# auduino.net
KiCad netlist of a schematic drawn in EAGLE
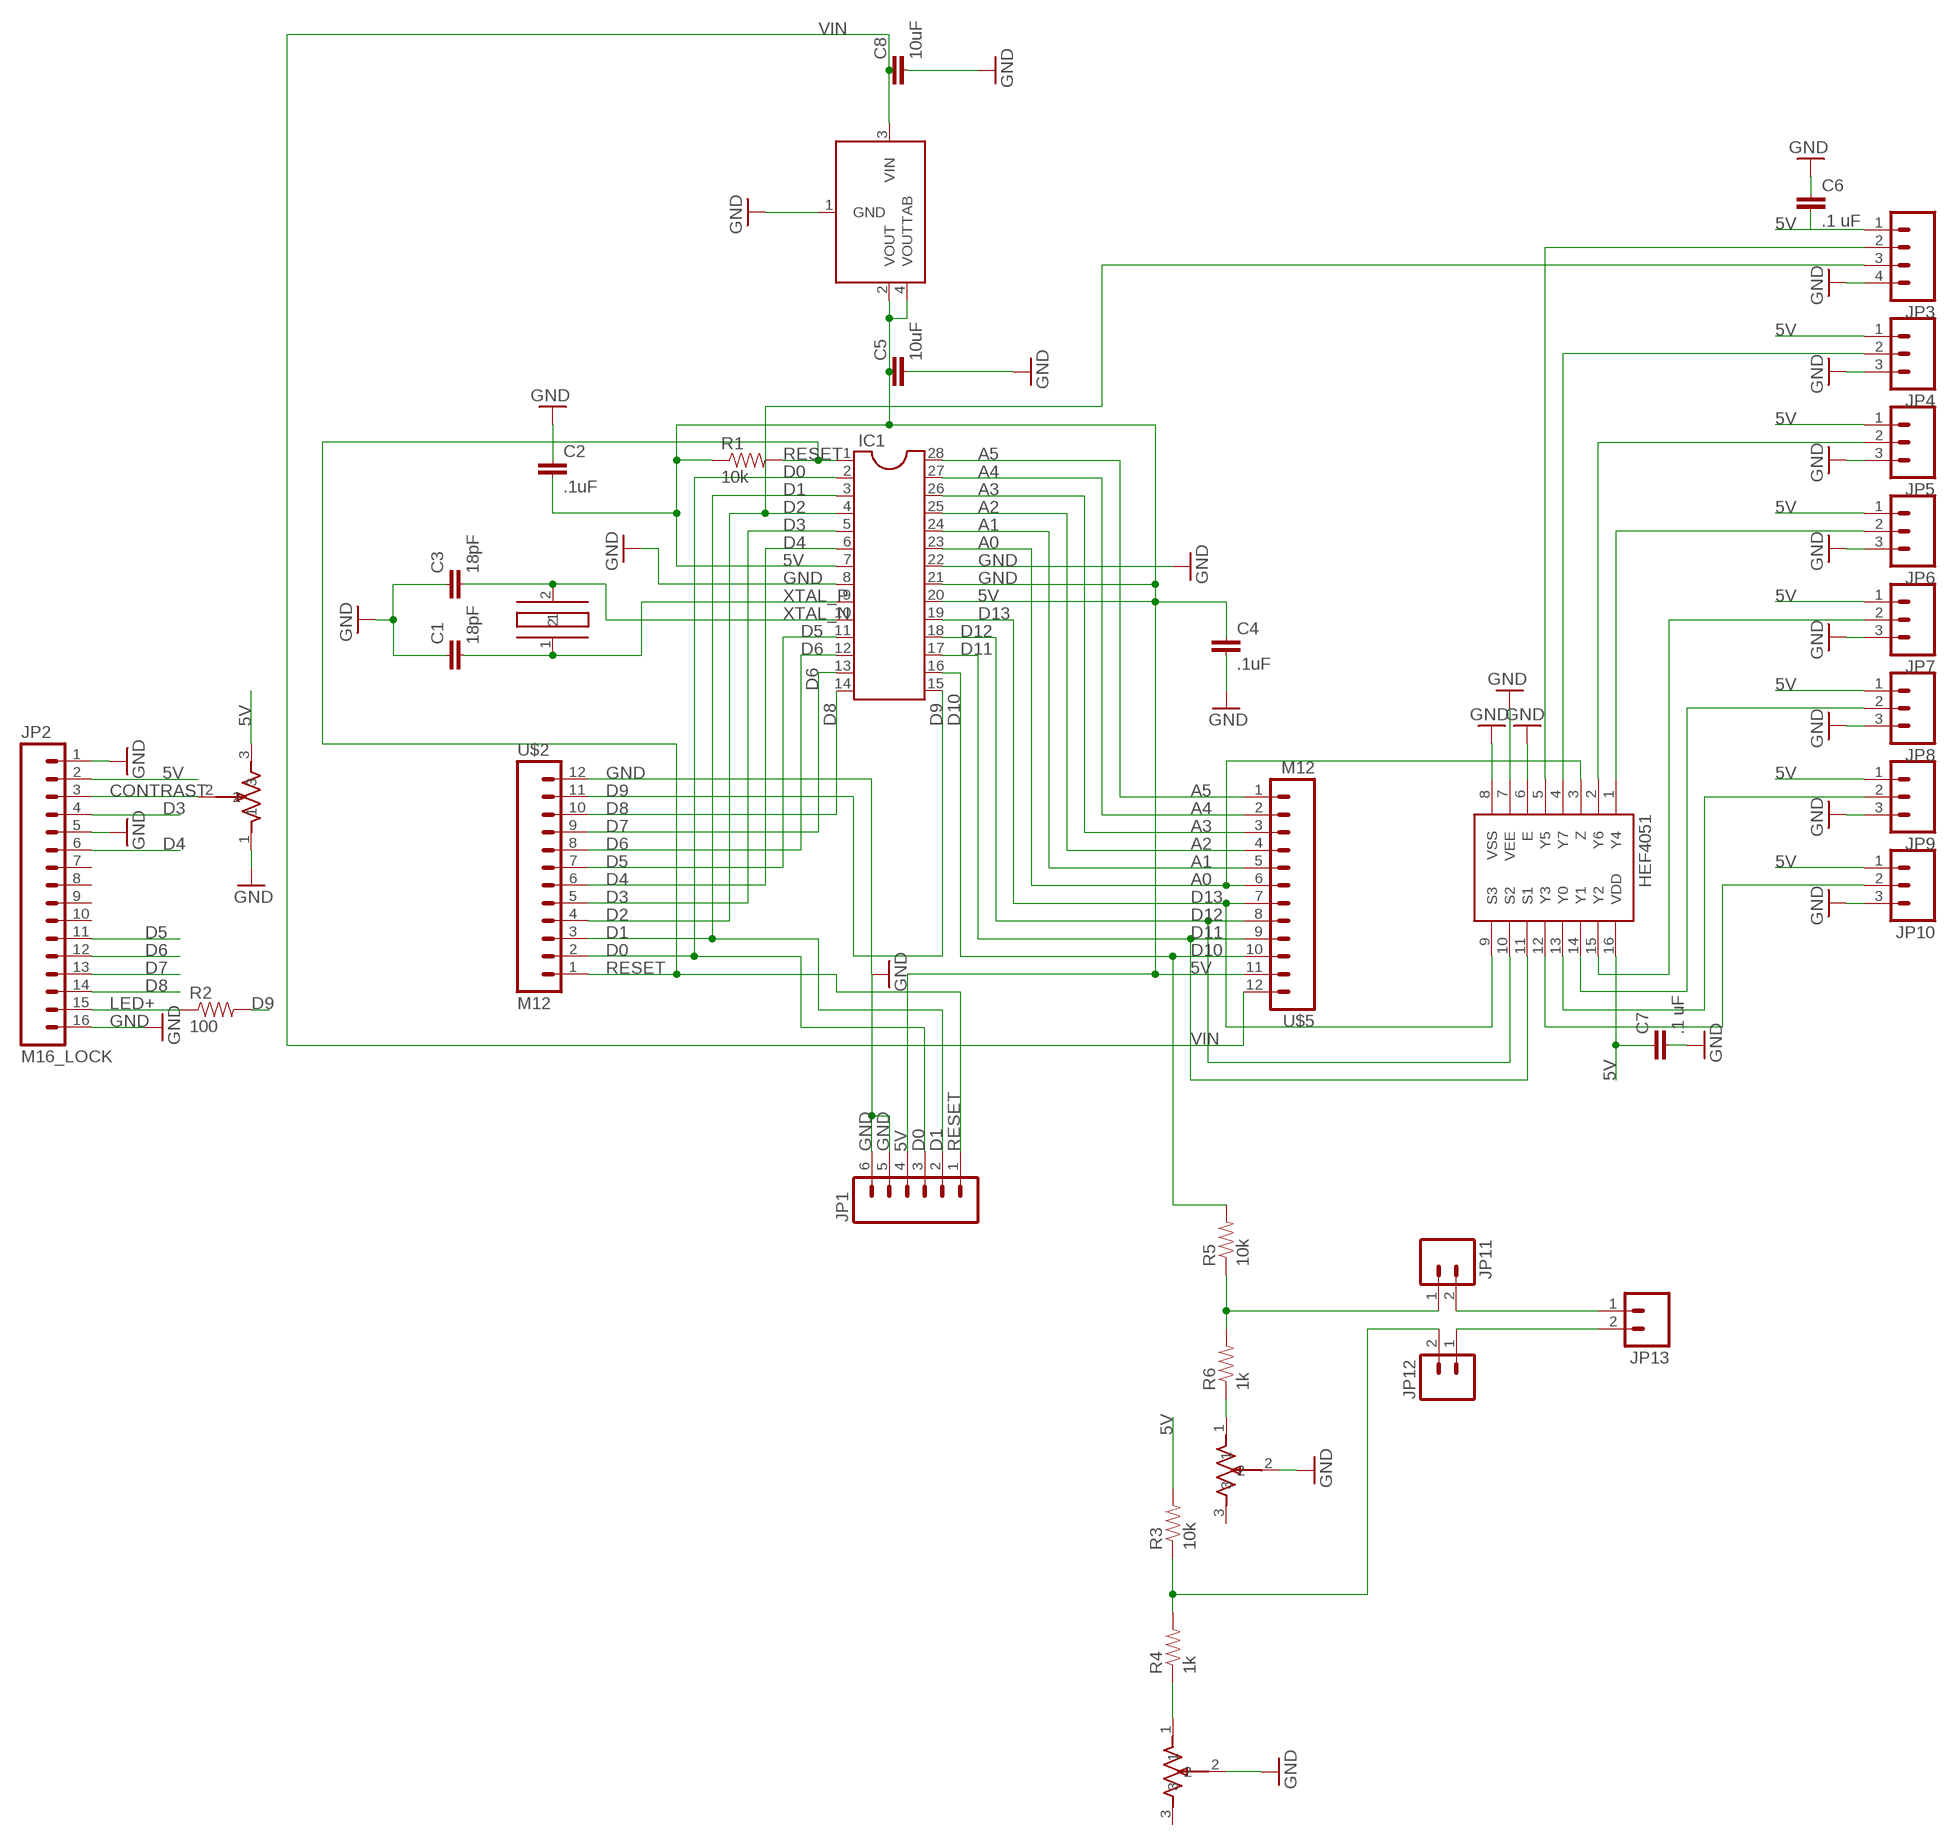
[diagram p0: schematic, sheet 1]

(export (version "E")
  (design (tool "Eeschema 10.0.6"))
  (components
    (comp (ref "5V")
      (value "ZLDO1117")
      (footprint "eagle-import:ZLDO1117")
      (libsource (lib "eagle-import") (part "ZLDO1117"))
    )
    (comp (ref "C1")
      (value "18pF")
      (footprint "eagle-import:0603-CAP")
      (libsource (lib "eagle-import") (part "CAP0603-CAP"))
    )
    (comp (ref "C2")
      (value ".1uF")
      (footprint "eagle-import:0805")
      (libsource (lib "eagle-import") (part "CAP0805"))
    )
    (comp (ref "C3")
      (value "18pF")
      (footprint "eagle-import:0603-CAP")
      (libsource (lib "eagle-import") (part "CAP0603-CAP"))
    )
    (comp (ref "C4")
      (value ".1uF")
      (footprint "eagle-import:0805")
      (libsource (lib "eagle-import") (part "CAP0805"))
    )
    (comp (ref "C5")
      (value "10uF")
      (footprint "eagle-import:1206")
      (libsource (lib "eagle-import") (part "CAP1206"))
    )
    (comp (ref "C6")
      (value ".1 uF")
      (footprint "eagle-import:0805")
      (libsource (lib "eagle-import") (part "CAP0805"))
    )
    (comp (ref "C7")
      (value ".1 uF")
      (footprint "eagle-import:0805")
      (libsource (lib "eagle-import") (part "CAP0805"))
    )
    (comp (ref "C8")
      (value "10uF")
      (footprint "eagle-import:1206")
      (libsource (lib "eagle-import") (part "CAP1206"))
    )
    (comp (ref "IC1")
      (value "DIL28-3")
      (footprint "eagle-import:DIL28-3")
      (libsource (lib "eagle-import") (part "DIL28-3"))
    )
    (comp (ref "JP1")
      (value "M06LOCK")
      (footprint "eagle-import:1X06_LOCK")
      (libsource (lib "eagle-import") (part "M06LOCK"))
    )
    (comp (ref "JP2")
      (value "M16_LOCK")
      (footprint "eagle-import:1X16_LOCK")
      (libsource (lib "eagle-import") (part "M16_LOCK"))
    )
    (comp (ref "JP3")
      (value "M04LOCK")
      (footprint "eagle-import:1X04_LOCK")
      (libsource (lib "eagle-import") (part "M04LOCK"))
    )
    (comp (ref "JP4")
      (value "M03LOCK")
      (footprint "eagle-import:1X03_LOCK")
      (libsource (lib "eagle-import") (part "M03LOCK"))
    )
    (comp (ref "JP5")
      (value "M03LOCK")
      (footprint "eagle-import:1X03_LOCK")
      (libsource (lib "eagle-import") (part "M03LOCK"))
    )
    (comp (ref "JP6")
      (value "M03LOCK")
      (footprint "eagle-import:1X03_LOCK")
      (libsource (lib "eagle-import") (part "M03LOCK"))
    )
    (comp (ref "JP7")
      (value "M03LOCK")
      (footprint "eagle-import:1X03_LOCK")
      (libsource (lib "eagle-import") (part "M03LOCK"))
    )
    (comp (ref "JP8")
      (value "M03LOCK")
      (footprint "eagle-import:1X03_LOCK")
      (libsource (lib "eagle-import") (part "M03LOCK"))
    )
    (comp (ref "JP9")
      (value "M03LOCK")
      (footprint "eagle-import:1X03_LOCK")
      (libsource (lib "eagle-import") (part "M03LOCK"))
    )
    (comp (ref "JP10")
      (value "M03LOCK")
      (footprint "eagle-import:1X03_LOCK")
      (libsource (lib "eagle-import") (part "M03LOCK"))
    )
    (comp (ref "JP11")
      (value "M02LOCK")
      (footprint "eagle-import:1X02_LOCK")
      (libsource (lib "eagle-import") (part "M02LOCK"))
    )
    (comp (ref "JP12")
      (value "M02LOCK")
      (footprint "eagle-import:1X02_LOCK")
      (libsource (lib "eagle-import") (part "M02LOCK"))
    )
    (comp (ref "JP13")
      (value "M02LOCK")
      (footprint "eagle-import:1X02_LOCK")
      (libsource (lib "eagle-import") (part "M02LOCK"))
    )
    (comp (ref "R1")
      (value "10k")
      (footprint "eagle-import:0805")
      (libsource (lib "eagle-import") (part "RESISTOR"))
    )
    (comp (ref "R2")
      (value "100")
      (footprint "eagle-import:0805")
      (libsource (lib "eagle-import") (part "RESISTOR"))
    )
    (comp (ref "R3")
      (value "10k")
      (footprint "eagle-import:0805")
      (libsource (lib "eagle-import") (part "RESISTOR"))
    )
    (comp (ref "R4")
      (value "1k")
      (footprint "eagle-import:0805")
      (libsource (lib "eagle-import") (part "RESISTOR"))
    )
    (comp (ref "R5")
      (value "10k")
      (footprint "eagle-import:0805")
      (libsource (lib "eagle-import") (part "RESISTOR"))
    )
    (comp (ref "R6")
      (value "1k")
      (footprint "eagle-import:0805")
      (libsource (lib "eagle-import") (part "RESISTOR"))
    )
    (comp (ref "U$1")
      (value "HC49US")
      (footprint "eagle-import:HC49US")
      (libsource (lib "eagle-import") (part "HC49US"))
    )
    (comp (ref "U$2")
      (value "M12")
      (footprint "eagle-import:1X12_LOCK")
      (libsource (lib "eagle-import") (part "M12LOCK"))
    )
    (comp (ref "U$3")
      (value "TRIMPOTTC33X-2")
      (footprint "eagle-import:TC33X-2")
      (libsource (lib "eagle-import") (part "TRIMPOTTC33X-2"))
    )
    (comp (ref "U$4")
      (value "NXP|HEF4051BTD")
      (footprint "eagle-import:SO16")
      (libsource (lib "eagle-import") (part "NXP|HEF4051BTD"))
    )
    (comp (ref "U$5")
      (value "M12")
      (footprint "eagle-import:1X12_LOCK")
      (libsource (lib "eagle-import") (part "M12LOCK"))
    )
    (comp (ref "U$6")
      (value "TRIMPOTTC33X-2")
      (footprint "eagle-import:TC33X-2")
      (libsource (lib "eagle-import") (part "TRIMPOTTC33X-2"))
    )
    (comp (ref "U$7")
      (value "TRIMPOTTC33X-2")
      (footprint "eagle-import:TC33X-2")
      (libsource (lib "eagle-import") (part "TRIMPOTTC33X-2"))
    )
  )
  (nets
    (net (code "1") (name "/5V") (class "Default")
      (node (ref "5V") (pin "2") (pinfunction "VOUT_2") (pintype "bidirectional"))
      (node (ref "5V") (pin "4") (pinfunction "VOUTTAB_4") (pintype "bidirectional"))
      (node (ref "C2") (pin "2") (pinfunction "2_2") (pintype "passive"))
      (node (ref "C4") (pin "1") (pinfunction "1_1") (pintype "passive"))
      (node (ref "C5") (pin "1") (pinfunction "1_1") (pintype "passive"))
      (node (ref "C6") (pin "2") (pinfunction "2_2") (pintype "passive"))
      (node (ref "C7") (pin "1") (pinfunction "1_1") (pintype "passive"))
      (node (ref "IC1") (pin "20") (pinfunction "20_20") (pintype "passive"))
      (node (ref "IC1") (pin "21") (pinfunction "21_21") (pintype "passive"))
      (node (ref "IC1") (pin "7") (pinfunction "7_7") (pintype "passive"))
      (node (ref "JP1") (pin "4") (pinfunction "4_4") (pintype "passive"))
      (node (ref "JP10") (pin "1") (pinfunction "1_1") (pintype "passive"))
      (node (ref "JP2") (pin "2") (pinfunction "2_2") (pintype "passive"))
      (node (ref "JP3") (pin "1") (pinfunction "1_1") (pintype "passive"))
      (node (ref "JP4") (pin "1") (pinfunction "1_1") (pintype "passive"))
      (node (ref "JP5") (pin "1") (pinfunction "1_1") (pintype "passive"))
      (node (ref "JP6") (pin "1") (pinfunction "1_1") (pintype "passive"))
      (node (ref "JP7") (pin "1") (pinfunction "1_1") (pintype "passive"))
      (node (ref "JP8") (pin "1") (pinfunction "1_1") (pintype "passive"))
      (node (ref "JP9") (pin "1") (pinfunction "1_1") (pintype "passive"))
      (node (ref "R1") (pin "1") (pinfunction "1_1") (pintype "passive"))
      (node (ref "R3") (pin "2") (pinfunction "2_2") (pintype "passive"))
      (node (ref "U$3") (pin "3") (pinfunction "3_3") (pintype "bidirectional"))
      (node (ref "U$4") (pin "16") (pinfunction "VDD_16") (pintype "bidirectional"))
      (node (ref "U$5") (pin "11") (pinfunction "11_11") (pintype "passive"))
    )
    (net (code "2") (name "/A0") (class "Default")
      (node (ref "IC1") (pin "23") (pinfunction "23_23") (pintype "passive"))
      (node (ref "U$4") (pin "3") (pinfunction "Z_3") (pintype "bidirectional"))
      (node (ref "U$5") (pin "6") (pinfunction "6_6") (pintype "passive"))
    )
    (net (code "3") (name "/A1") (class "Default")
      (node (ref "IC1") (pin "24") (pinfunction "24_24") (pintype "passive"))
      (node (ref "U$5") (pin "5") (pinfunction "5_5") (pintype "passive"))
    )
    (net (code "4") (name "/A2") (class "Default")
      (node (ref "IC1") (pin "25") (pinfunction "25_25") (pintype "passive"))
      (node (ref "U$5") (pin "4") (pinfunction "4_4") (pintype "passive"))
    )
    (net (code "5") (name "/A3") (class "Default")
      (node (ref "IC1") (pin "26") (pinfunction "26_26") (pintype "passive"))
      (node (ref "U$5") (pin "3") (pinfunction "3_3") (pintype "passive"))
    )
    (net (code "6") (name "/A4") (class "Default")
      (node (ref "IC1") (pin "27") (pinfunction "27_27") (pintype "passive"))
      (node (ref "U$5") (pin "2") (pinfunction "2_2") (pintype "passive"))
    )
    (net (code "7") (name "/A5") (class "Default")
      (node (ref "IC1") (pin "28") (pinfunction "28_28") (pintype "passive"))
      (node (ref "U$5") (pin "1") (pinfunction "1_1") (pintype "passive"))
    )
    (net (code "8") (name "/CONTRAST") (class "Default")
      (node (ref "JP2") (pin "3") (pinfunction "3_3") (pintype "passive"))
      (node (ref "U$3") (pin "2") (pinfunction "2_2") (pintype "bidirectional"))
    )
    (net (code "9") (name "/D0") (class "Default")
      (node (ref "IC1") (pin "2") (pinfunction "2_2") (pintype "passive"))
      (node (ref "JP1") (pin "3") (pinfunction "3_3") (pintype "passive"))
      (node (ref "U$2") (pin "2") (pinfunction "2_2") (pintype "passive"))
    )
    (net (code "10") (name "/D1") (class "Default")
      (node (ref "IC1") (pin "3") (pinfunction "3_3") (pintype "passive"))
      (node (ref "JP1") (pin "2") (pinfunction "2_2") (pintype "passive"))
      (node (ref "U$2") (pin "3") (pinfunction "3_3") (pintype "passive"))
    )
    (net (code "11") (name "/D2") (class "Default")
      (node (ref "IC1") (pin "4") (pinfunction "4_4") (pintype "passive"))
      (node (ref "JP3") (pin "3") (pinfunction "3_3") (pintype "passive"))
      (node (ref "U$2") (pin "4") (pinfunction "4_4") (pintype "passive"))
    )
    (net (code "12") (name "/D3") (class "Default")
      (node (ref "IC1") (pin "5") (pinfunction "5_5") (pintype "passive"))
      (node (ref "JP2") (pin "4") (pinfunction "4_4") (pintype "passive"))
      (node (ref "U$2") (pin "5") (pinfunction "5_5") (pintype "passive"))
    )
    (net (code "13") (name "/D4") (class "Default")
      (node (ref "IC1") (pin "6") (pinfunction "6_6") (pintype "passive"))
      (node (ref "JP2") (pin "6") (pinfunction "6_6") (pintype "passive"))
      (node (ref "U$2") (pin "6") (pinfunction "6_6") (pintype "passive"))
    )
    (net (code "14") (name "/D5") (class "Default")
      (node (ref "IC1") (pin "11") (pinfunction "11_11") (pintype "passive"))
      (node (ref "JP2") (pin "11") (pinfunction "11_11") (pintype "passive"))
      (node (ref "U$2") (pin "7") (pinfunction "7_7") (pintype "passive"))
    )
    (net (code "15") (name "/D6") (class "Default")
      (node (ref "IC1") (pin "12") (pinfunction "12_12") (pintype "passive"))
      (node (ref "JP2") (pin "12") (pinfunction "12_12") (pintype "passive"))
      (node (ref "U$2") (pin "8") (pinfunction "8_8") (pintype "passive"))
    )
    (net (code "16") (name "/D7") (class "Default")
      (node (ref "IC1") (pin "13") (pinfunction "13_13") (pintype "passive"))
      (node (ref "JP2") (pin "13") (pinfunction "13_13") (pintype "passive"))
      (node (ref "U$2") (pin "9") (pinfunction "9_9") (pintype "passive"))
    )
    (net (code "17") (name "/D8") (class "Default")
      (node (ref "IC1") (pin "14") (pinfunction "14_14") (pintype "passive"))
      (node (ref "JP2") (pin "14") (pinfunction "14_14") (pintype "passive"))
      (node (ref "U$2") (pin "10") (pinfunction "10_10") (pintype "passive"))
    )
    (net (code "18") (name "/D9") (class "Default")
      (node (ref "IC1") (pin "15") (pinfunction "15_15") (pintype "passive"))
      (node (ref "R2") (pin "2") (pinfunction "2_2") (pintype "passive"))
      (node (ref "U$2") (pin "11") (pinfunction "11_11") (pintype "passive"))
    )
    (net (code "19") (name "/D10") (class "Default")
      (node (ref "IC1") (pin "16") (pinfunction "16_16") (pintype "passive"))
      (node (ref "R5") (pin "2") (pinfunction "2_2") (pintype "passive"))
      (node (ref "U$5") (pin "10") (pinfunction "10_10") (pintype "passive"))
    )
    (net (code "20") (name "/D11") (class "Default")
      (node (ref "IC1") (pin "17") (pinfunction "17_17") (pintype "passive"))
      (node (ref "U$4") (pin "11") (pinfunction "S1_11") (pintype "bidirectional"))
      (node (ref "U$5") (pin "9") (pinfunction "9_9") (pintype "passive"))
    )
    (net (code "21") (name "/D12") (class "Default")
      (node (ref "IC1") (pin "18") (pinfunction "18_18") (pintype "passive"))
      (node (ref "U$4") (pin "10") (pinfunction "S2_10") (pintype "bidirectional"))
      (node (ref "U$5") (pin "8") (pinfunction "8_8") (pintype "passive"))
    )
    (net (code "22") (name "/D13") (class "Default")
      (node (ref "IC1") (pin "19") (pinfunction "19_19") (pintype "passive"))
      (node (ref "U$4") (pin "9") (pinfunction "S3_9") (pintype "bidirectional"))
      (node (ref "U$5") (pin "7") (pinfunction "7_7") (pintype "passive"))
    )
    (net (code "23") (name "/LED+") (class "Default")
      (node (ref "JP2") (pin "15") (pinfunction "15_15") (pintype "passive"))
      (node (ref "R2") (pin "1") (pinfunction "1_1") (pintype "passive"))
    )
    (net (code "24") (name "/RESET") (class "Default")
      (node (ref "IC1") (pin "1") (pinfunction "1_1") (pintype "passive"))
      (node (ref "JP1") (pin "1") (pinfunction "1_1") (pintype "passive"))
      (node (ref "R1") (pin "2") (pinfunction "2_2") (pintype "passive"))
      (node (ref "U$2") (pin "1") (pinfunction "1_1") (pintype "passive"))
    )
    (net (code "25") (name "/VIN") (class "Default")
      (node (ref "5V") (pin "3") (pinfunction "VIN_3") (pintype "bidirectional"))
      (node (ref "C8") (pin "1") (pinfunction "1_1") (pintype "passive"))
      (node (ref "U$5") (pin "12") (pinfunction "12_12") (pintype "passive"))
    )
    (net (code "26") (name "/XTAL_N") (class "Default")
      (node (ref "C3") (pin "2") (pinfunction "2_2") (pintype "passive"))
      (node (ref "IC1") (pin "10") (pinfunction "10_10") (pintype "passive"))
      (node (ref "U$1") (pin "2") (pinfunction "2_2") (pintype "bidirectional"))
    )
    (net (code "27") (name "/XTAL_P") (class "Default")
      (node (ref "C1") (pin "2") (pinfunction "2_2") (pintype "passive"))
      (node (ref "IC1") (pin "9") (pinfunction "9_9") (pintype "passive"))
      (node (ref "U$1") (pin "1") (pinfunction "1_1") (pintype "bidirectional"))
    )
    (net (code "28") (name "GND") (class "Default")
      (node (ref "5V") (pin "1") (pinfunction "GND_1") (pintype "bidirectional"))
      (node (ref "C1") (pin "1") (pinfunction "1_1") (pintype "passive"))
      (node (ref "C2") (pin "1") (pinfunction "1_1") (pintype "passive"))
      (node (ref "C3") (pin "1") (pinfunction "1_1") (pintype "passive"))
      (node (ref "C4") (pin "2") (pinfunction "2_2") (pintype "passive"))
      (node (ref "C5") (pin "2") (pinfunction "2_2") (pintype "passive"))
      (node (ref "C6") (pin "1") (pinfunction "1_1") (pintype "passive"))
      (node (ref "C7") (pin "2") (pinfunction "2_2") (pintype "passive"))
      (node (ref "C8") (pin "2") (pinfunction "2_2") (pintype "passive"))
      (node (ref "IC1") (pin "22") (pinfunction "22_22") (pintype "passive"))
      (node (ref "IC1") (pin "8") (pinfunction "8_8") (pintype "passive"))
      (node (ref "JP1") (pin "5") (pinfunction "5_5") (pintype "passive"))
      (node (ref "JP1") (pin "6") (pinfunction "6_6") (pintype "passive"))
      (node (ref "JP10") (pin "3") (pinfunction "3_3") (pintype "passive"))
      (node (ref "JP2") (pin "1") (pinfunction "1_1") (pintype "passive"))
      (node (ref "JP2") (pin "16") (pinfunction "16_16") (pintype "passive"))
      (node (ref "JP2") (pin "5") (pinfunction "5_5") (pintype "passive"))
      (node (ref "JP3") (pin "4") (pinfunction "4_4") (pintype "passive"))
      (node (ref "JP4") (pin "3") (pinfunction "3_3") (pintype "passive"))
      (node (ref "JP5") (pin "3") (pinfunction "3_3") (pintype "passive"))
      (node (ref "JP6") (pin "3") (pinfunction "3_3") (pintype "passive"))
      (node (ref "JP7") (pin "3") (pinfunction "3_3") (pintype "passive"))
      (node (ref "JP8") (pin "3") (pinfunction "3_3") (pintype "passive"))
      (node (ref "JP9") (pin "3") (pinfunction "3_3") (pintype "passive"))
      (node (ref "U$2") (pin "12") (pinfunction "12_12") (pintype "passive"))
      (node (ref "U$3") (pin "1") (pinfunction "1_1") (pintype "bidirectional"))
      (node (ref "U$4") (pin "6") (pinfunction "E_6") (pintype "bidirectional"))
      (node (ref "U$4") (pin "7") (pinfunction "VEE_7") (pintype "bidirectional"))
      (node (ref "U$4") (pin "8") (pinfunction "VSS_8") (pintype "bidirectional"))
      (node (ref "U$6") (pin "2") (pinfunction "2_2") (pintype "bidirectional"))
      (node (ref "U$7") (pin "2") (pinfunction "2_2") (pintype "bidirectional"))
    )
    (net (code "29") (name "Net-(JP11-Pad1)") (class "Default")
      (node (ref "JP11") (pin "1") (pinfunction "1_1") (pintype "passive"))
      (node (ref "R5") (pin "1") (pinfunction "1_1") (pintype "passive"))
      (node (ref "R6") (pin "2") (pinfunction "2_2") (pintype "passive"))
    )
    (net (code "30") (name "Net-(JP11-Pad2)") (class "Default")
      (node (ref "JP11") (pin "2") (pinfunction "2_2") (pintype "passive"))
      (node (ref "JP13") (pin "1") (pinfunction "1_1") (pintype "passive"))
    )
    (net (code "31") (name "Net-(JP12-Pad1)") (class "Default")
      (node (ref "JP12") (pin "1") (pinfunction "1_1") (pintype "passive"))
      (node (ref "JP13") (pin "2") (pinfunction "2_2") (pintype "passive"))
    )
    (net (code "32") (name "Net-(JP12-Pad2)") (class "Default")
      (node (ref "JP12") (pin "2") (pinfunction "2_2") (pintype "passive"))
      (node (ref "R3") (pin "1") (pinfunction "1_1") (pintype "passive"))
      (node (ref "R4") (pin "2") (pinfunction "2_2") (pintype "passive"))
    )
    (net (code "33") (name "Net-(R4-Pad1)") (class "Default")
      (node (ref "R4") (pin "1") (pinfunction "1_1") (pintype "passive"))
      (node (ref "U$6") (pin "1") (pinfunction "1_1") (pintype "bidirectional"))
    )
    (net (code "34") (name "Net-(R6-Pad1)") (class "Default")
      (node (ref "R6") (pin "1") (pinfunction "1_1") (pintype "passive"))
      (node (ref "U$7") (pin "1") (pinfunction "1_1") (pintype "bidirectional"))
    )
    (net (code "35") (name "Net-(U$4-Y0)") (class "Default")
      (node (ref "JP9") (pin "2") (pinfunction "2_2") (pintype "passive"))
      (node (ref "U$4") (pin "13") (pinfunction "Y0_13") (pintype "bidirectional"))
    )
    (net (code "36") (name "Net-(U$4-Y1)") (class "Default")
      (node (ref "JP8") (pin "2") (pinfunction "2_2") (pintype "passive"))
      (node (ref "U$4") (pin "14") (pinfunction "Y1_14") (pintype "bidirectional"))
    )
    (net (code "37") (name "Net-(U$4-Y2)") (class "Default")
      (node (ref "JP7") (pin "2") (pinfunction "2_2") (pintype "passive"))
      (node (ref "U$4") (pin "15") (pinfunction "Y2_15") (pintype "bidirectional"))
    )
    (net (code "38") (name "Net-(U$4-Y3)") (class "Default")
      (node (ref "JP10") (pin "2") (pinfunction "2_2") (pintype "passive"))
      (node (ref "U$4") (pin "12") (pinfunction "Y3_12") (pintype "bidirectional"))
    )
    (net (code "39") (name "Net-(U$4-Y4)") (class "Default")
      (node (ref "JP6") (pin "2") (pinfunction "2_2") (pintype "passive"))
      (node (ref "U$4") (pin "1") (pinfunction "Y4_1") (pintype "bidirectional"))
    )
    (net (code "40") (name "Net-(U$4-Y5)") (class "Default")
      (node (ref "JP3") (pin "2") (pinfunction "2_2") (pintype "passive"))
      (node (ref "U$4") (pin "5") (pinfunction "Y5_5") (pintype "bidirectional"))
    )
    (net (code "41") (name "Net-(U$4-Y6)") (class "Default")
      (node (ref "JP5") (pin "2") (pinfunction "2_2") (pintype "passive"))
      (node (ref "U$4") (pin "2") (pinfunction "Y6_2") (pintype "bidirectional"))
    )
    (net (code "42") (name "Net-(U$4-Y7)") (class "Default")
      (node (ref "JP4") (pin "2") (pinfunction "2_2") (pintype "passive"))
      (node (ref "U$4") (pin "4") (pinfunction "Y7_4") (pintype "bidirectional"))
    )
    (net (code "43") (name "unconnected-(JP2-Pad7)") (class "Default")
      (node (ref "JP2") (pin "7") (pinfunction "7_7") (pintype "passive"))
    )
    (net (code "44") (name "unconnected-(JP2-Pad8)") (class "Default")
      (node (ref "JP2") (pin "8") (pinfunction "8_8") (pintype "passive"))
    )
    (net (code "45") (name "unconnected-(JP2-Pad9)") (class "Default")
      (node (ref "JP2") (pin "9") (pinfunction "9_9") (pintype "passive"))
    )
    (net (code "46") (name "unconnected-(JP2-Pad10)") (class "Default")
      (node (ref "JP2") (pin "10") (pinfunction "10_10") (pintype "passive"))
    )
    (net (code "47") (name "unconnected-(U$6-Pad3)") (class "Default")
      (node (ref "U$6") (pin "3") (pinfunction "3_3") (pintype "bidirectional"))
    )
    (net (code "48") (name "unconnected-(U$7-Pad3)") (class "Default")
      (node (ref "U$7") (pin "3") (pinfunction "3_3") (pintype "bidirectional"))
    )
  )
)
